# interface.net
KiCad netlist of a schematic drawn in Altium Designer
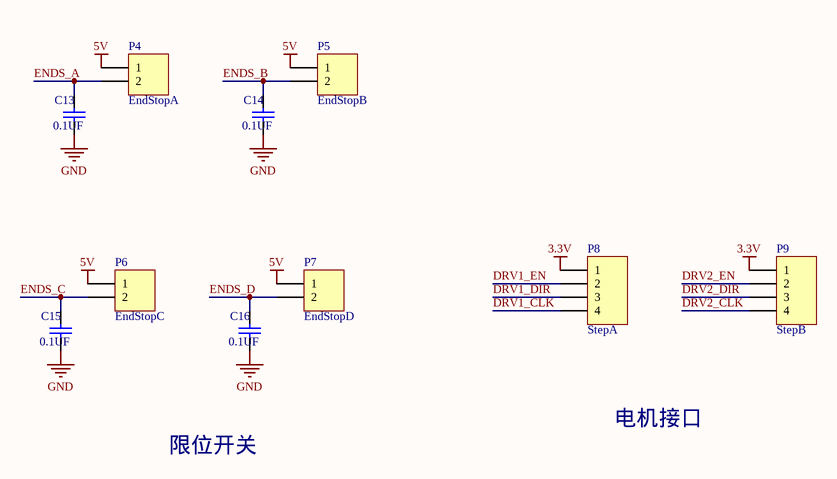
[diagram p0: interface.SchDoc]

(export (version "E")
  (design (tool "Eeschema 10.0.6"))
  (components
    (comp (ref "C13")
      (value "0.1UF")
      (footprint "0603(1608)")
      (description "Capacitor")
      (fields (field (name "PUBLISHER") "Altium Limited"))
      (libsource (lib "*") (part "Cap"))
    )
    (comp (ref "C14")
      (value "0.1UF")
      (footprint "0603(1608)")
      (description "Capacitor")
      (fields (field (name "PUBLISHER") "Altium Limited"))
      (libsource (lib "*") (part "Cap"))
    )
    (comp (ref "C15")
      (value "0.1UF")
      (footprint "0603(1608)")
      (description "Capacitor")
      (fields (field (name "PUBLISHER") "Altium Limited"))
      (libsource (lib "*") (part "Cap"))
    )
    (comp (ref "C16")
      (value "0.1UF")
      (footprint "0603(1608)")
      (description "Capacitor")
      (fields (field (name "PUBLISHER") "Altium Limited"))
      (libsource (lib "*") (part "Cap"))
    )
    (comp (ref "P4")
      (value "EndStopA")
      (footprint "XH2.54_2PIN")
      (description "Header, 2-Pin")
      (fields (field (name "PUBLISHER") "Altium Limited"))
      (libsource (lib "Miscellaneous Connectors") (part "Header 2"))
    )
    (comp (ref "P5")
      (value "EndStopB")
      (footprint "XH2.54_2PIN")
      (description "Header, 2-Pin")
      (fields (field (name "PUBLISHER") "Altium Limited"))
      (libsource (lib "Miscellaneous Connectors") (part "Header 2"))
    )
    (comp (ref "P6")
      (value "EndStopC")
      (footprint "XH2.54_2PIN")
      (description "Header, 2-Pin")
      (fields (field (name "PUBLISHER") "Altium Limited"))
      (libsource (lib "Miscellaneous Connectors") (part "Header 2"))
    )
    (comp (ref "P7")
      (value "EndStopD")
      (footprint "XH2.54_2PIN")
      (description "Header, 2-Pin")
      (fields (field (name "PUBLISHER") "Altium Limited"))
      (libsource (lib "Miscellaneous Connectors") (part "Header 2"))
    )
    (comp (ref "P8")
      (value "StepA")
      (footprint "XH2.54_4PIN")
      (description "Header, 4-Pin")
      (fields (field (name "PUBLISHER") "Altium Limited"))
      (libsource (lib "Miscellaneous Connectors") (part "Header 4"))
    )
    (comp (ref "P9")
      (value "StepB")
      (footprint "XH2.54_4PIN")
      (description "Header, 4-Pin")
      (fields (field (name "PUBLISHER") "Altium Limited"))
      (libsource (lib "Miscellaneous Connectors") (part "Header 4"))
    )
  )
  (nets
    (net (code "1") (name "/DRV1_CLK") (class "Default")
      (node (ref "P8") (pin "4") (pinfunction "4_4") (pintype "passive"))
    )
    (net (code "2") (name "/DRV1_DIR") (class "Default")
      (node (ref "P8") (pin "3") (pinfunction "3_3") (pintype "passive"))
    )
    (net (code "3") (name "/DRV1_EN") (class "Default")
      (node (ref "P8") (pin "2") (pinfunction "2_2") (pintype "passive"))
    )
    (net (code "4") (name "/DRV2_CLK") (class "Default")
      (node (ref "P9") (pin "4") (pinfunction "4_4") (pintype "passive"))
    )
    (net (code "5") (name "/DRV2_DIR") (class "Default")
      (node (ref "P9") (pin "3") (pinfunction "3_3") (pintype "passive"))
    )
    (net (code "6") (name "/DRV2_EN") (class "Default")
      (node (ref "P9") (pin "2") (pinfunction "2_2") (pintype "passive"))
    )
    (net (code "7") (name "/ENDS_A") (class "Default")
      (node (ref "C13") (pin "1") (pinfunction "1_1") (pintype "passive"))
      (node (ref "P4") (pin "2") (pinfunction "2_2") (pintype "passive"))
    )
    (net (code "8") (name "/ENDS_B") (class "Default")
      (node (ref "C14") (pin "1") (pinfunction "1_1") (pintype "passive"))
      (node (ref "P5") (pin "2") (pinfunction "2_2") (pintype "passive"))
    )
    (net (code "9") (name "/ENDS_C") (class "Default")
      (node (ref "C15") (pin "1") (pinfunction "1_1") (pintype "passive"))
      (node (ref "P6") (pin "2") (pinfunction "2_2") (pintype "passive"))
    )
    (net (code "10") (name "/ENDS_D") (class "Default")
      (node (ref "C16") (pin "1") (pinfunction "1_1") (pintype "passive"))
      (node (ref "P7") (pin "2") (pinfunction "2_2") (pintype "passive"))
    )
    (net (code "11") (name "3.3V") (class "Default")
      (node (ref "P8") (pin "1") (pinfunction "1_1") (pintype "passive"))
      (node (ref "P9") (pin "1") (pinfunction "1_1") (pintype "passive"))
    )
    (net (code "12") (name "5V") (class "Default")
      (node (ref "P4") (pin "1") (pinfunction "1_1") (pintype "passive"))
      (node (ref "P5") (pin "1") (pinfunction "1_1") (pintype "passive"))
      (node (ref "P6") (pin "1") (pinfunction "1_1") (pintype "passive"))
      (node (ref "P7") (pin "1") (pinfunction "1_1") (pintype "passive"))
    )
    (net (code "13") (name "GND") (class "Default")
      (node (ref "C13") (pin "2") (pinfunction "2_2") (pintype "passive"))
      (node (ref "C14") (pin "2") (pinfunction "2_2") (pintype "passive"))
      (node (ref "C15") (pin "2") (pinfunction "2_2") (pintype "passive"))
      (node (ref "C16") (pin "2") (pinfunction "2_2") (pintype "passive"))
    )
  )
)
